# Circuit.net
KiCad netlist of a schematic drawn in EAGLE
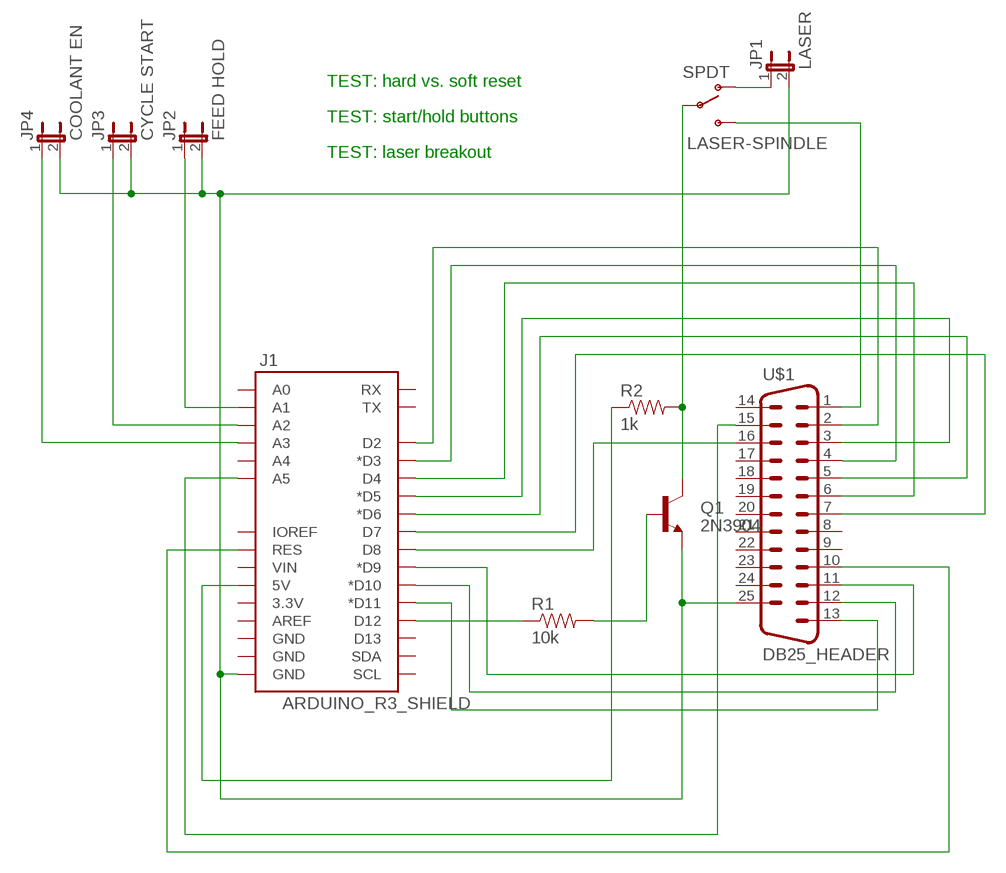
[diagram p0: schematic, sheet 1]

(export (version "E")
  (design (tool "Eeschema 10.0.6"))
  (components
    (comp (ref "J1")
      (value "ARDUINO_R3_SHIELD")
      (footprint "eagle-import:UNO_R3_SHIELD")
      (libsource (lib "eagle-import") (part "ARDUINO_R3_SHIELD"))
    )
    (comp (ref "JP1")
      (value "LASER")
      (footprint "eagle-import:1X02")
      (libsource (lib "eagle-import") (part "JUMPER-2PTH"))
    )
    (comp (ref "JP2")
      (value "FEED HOLD")
      (footprint "eagle-import:1X02")
      (libsource (lib "eagle-import") (part "JUMPER-2PTH"))
    )
    (comp (ref "JP3")
      (value "CYCLE START")
      (footprint "eagle-import:1X02")
      (libsource (lib "eagle-import") (part "JUMPER-2PTH"))
    )
    (comp (ref "JP4")
      (value "COOLANT EN")
      (footprint "eagle-import:1X02")
      (libsource (lib "eagle-import") (part "JUMPER-2PTH"))
    )
    (comp (ref "LASER-SPINDLE")
      (value "SPDT")
      (footprint "eagle-import:SWITCH-SPDT")
      (libsource (lib "eagle-import") (part "SWITCH-SPDTPTH"))
    )
    (comp (ref "Q1")
      (value "2N3904")
      (footprint "eagle-import:TO-92-AMMO")
      (libsource (lib "eagle-import") (part "TRANSISTOR_NPNBC547"))
    )
    (comp (ref "R1")
      (value "10k")
      (footprint "eagle-import:AXIAL-0.4")
      (libsource (lib "eagle-import") (part "RESISTORPTH-1/4W"))
    )
    (comp (ref "R2")
      (value "1k")
      (footprint "eagle-import:AXIAL-0.4")
      (libsource (lib "eagle-import") (part "RESISTORPTH-1/4W"))
    )
    (comp (ref "U$1")
      (value "DB25_HEADER")
      (footprint "eagle-import:DB25_HEADER")
      (libsource (lib "eagle-import") (part "DB25_HEADER"))
    )
  )
  (nets
    (net (code "1") (name "Net-(J1-*D3)") (class "Default")
      (node (ref "J1") (pin "D3") (pinfunction "*D3_D3") (pintype "bidirectional"))
      (node (ref "U$1") (pin "4") (pinfunction "4_4") (pintype "passive"))
    )
    (net (code "2") (name "Net-(J1-*D5)") (class "Default")
      (node (ref "J1") (pin "D5") (pinfunction "*D5_D5") (pintype "bidirectional"))
      (node (ref "U$1") (pin "3") (pinfunction "3_3") (pintype "passive"))
    )
    (net (code "3") (name "Net-(J1-*D6)") (class "Default")
      (node (ref "J1") (pin "D6") (pinfunction "*D6_D6") (pintype "bidirectional"))
      (node (ref "U$1") (pin "5") (pinfunction "5_5") (pintype "passive"))
    )
    (net (code "4") (name "Net-(J1-*D9)") (class "Default")
      (node (ref "J1") (pin "D9") (pinfunction "*D9_D9") (pintype "bidirectional"))
      (node (ref "U$1") (pin "11") (pinfunction "11_11") (pintype "passive"))
    )
    (net (code "5") (name "Net-(J1-*D10)") (class "Default")
      (node (ref "J1") (pin "D10") (pinfunction "*D10_D10") (pintype "bidirectional"))
      (node (ref "U$1") (pin "12") (pinfunction "12_12") (pintype "passive"))
    )
    (net (code "6") (name "Net-(J1-*D11)") (class "Default")
      (node (ref "J1") (pin "D11") (pinfunction "*D11_D11") (pintype "bidirectional"))
      (node (ref "U$1") (pin "13") (pinfunction "13_13") (pintype "passive"))
    )
    (net (code "7") (name "Net-(J1-PadA1)") (class "Default")
      (node (ref "J1") (pin "A1") (pinfunction "A1_A1") (pintype "bidirectional"))
      (node (ref "JP2") (pin "1") (pinfunction "1_1") (pintype "passive"))
    )
    (net (code "8") (name "Net-(J1-PadA2)") (class "Default")
      (node (ref "J1") (pin "A2") (pinfunction "A2_A2") (pintype "bidirectional"))
      (node (ref "JP3") (pin "1") (pinfunction "1_1") (pintype "passive"))
    )
    (net (code "9") (name "Net-(J1-PadA3)") (class "Default")
      (node (ref "J1") (pin "A3") (pinfunction "A3_A3") (pintype "bidirectional"))
      (node (ref "JP4") (pin "1") (pinfunction "1_1") (pintype "passive"))
    )
    (net (code "10") (name "Net-(J1-PadA5)") (class "Default")
      (node (ref "J1") (pin "A5") (pinfunction "A5_A5") (pintype "bidirectional"))
      (node (ref "U$1") (pin "15") (pinfunction "15_15") (pintype "passive"))
    )
    (net (code "11") (name "Net-(J1-PadD2)") (class "Default")
      (node (ref "J1") (pin "D2") (pinfunction "D2_D2") (pintype "bidirectional"))
      (node (ref "U$1") (pin "2") (pinfunction "2_2") (pintype "passive"))
    )
    (net (code "12") (name "Net-(J1-PadD4)") (class "Default")
      (node (ref "J1") (pin "D4") (pinfunction "D4_D4") (pintype "bidirectional"))
      (node (ref "U$1") (pin "6") (pinfunction "6_6") (pintype "passive"))
    )
    (net (code "13") (name "Net-(J1-PadD7)") (class "Default")
      (node (ref "J1") (pin "D7") (pinfunction "D7_D7") (pintype "bidirectional"))
      (node (ref "U$1") (pin "7") (pinfunction "7_7") (pintype "passive"))
    )
    (net (code "14") (name "Net-(J1-PadD8)") (class "Default")
      (node (ref "J1") (pin "D8") (pinfunction "D8_D8") (pintype "bidirectional"))
      (node (ref "U$1") (pin "16") (pinfunction "16_16") (pintype "passive"))
    )
    (net (code "15") (name "Net-(J1-PadRES)") (class "Default")
      (node (ref "J1") (pin "RES") (pinfunction "RES_RES") (pintype "bidirectional"))
      (node (ref "U$1") (pin "10") (pinfunction "10_10") (pintype "passive"))
    )
    (net (code "16") (name "Net-(LASER-SPINDLE-O)") (class "Default")
      (node (ref "JP1") (pin "1") (pinfunction "1_1") (pintype "passive"))
      (node (ref "LASER-SPINDLE") (pin "1") (pinfunction "O_1") (pintype "passive"))
    )
    (net (code "17") (name "Net-(LASER-SPINDLE-P)") (class "Default")
      (node (ref "LASER-SPINDLE") (pin "2") (pinfunction "P_2") (pintype "passive"))
      (node (ref "Q1") (pin "1") (pinfunction "C_1") (pintype "passive"))
      (node (ref "R2") (pin "P$2") (pinfunction "2_P$2") (pintype "passive"))
    )
    (net (code "18") (name "Net-(LASER-SPINDLE-S)") (class "Default")
      (node (ref "LASER-SPINDLE") (pin "3") (pinfunction "S_3") (pintype "passive"))
      (node (ref "U$1") (pin "1") (pinfunction "1_1") (pintype "passive"))
    )
    (net (code "19") (name "Net-(Q1-B)") (class "Default")
      (node (ref "Q1") (pin "2") (pinfunction "B_2") (pintype "passive"))
      (node (ref "R1") (pin "P$2") (pinfunction "2_P$2") (pintype "passive"))
    )
    (net (code "20") (name "Net-(Q1-E)") (class "Default")
      (node (ref "J1") (pin "GND@0") (pinfunction "GND_GND@0") (pintype "bidirectional"))
      (node (ref "JP1") (pin "2") (pinfunction "2_2") (pintype "passive"))
      (node (ref "JP2") (pin "2") (pinfunction "2_2") (pintype "passive"))
      (node (ref "JP3") (pin "2") (pinfunction "2_2") (pintype "passive"))
      (node (ref "JP4") (pin "2") (pinfunction "2_2") (pintype "passive"))
      (node (ref "Q1") (pin "3") (pinfunction "E_3") (pintype "passive"))
      (node (ref "U$1") (pin "25") (pinfunction "25_25") (pintype "passive"))
    )
    (net (code "21") (name "Net-(R1-1)") (class "Default")
      (node (ref "J1") (pin "D12") (pinfunction "D12_D12") (pintype "bidirectional"))
      (node (ref "R1") (pin "P$1") (pinfunction "1_P$1") (pintype "passive"))
    )
    (net (code "22") (name "Net-(R2-1)") (class "Default")
      (node (ref "J1") (pin "5V") (pinfunction "5V_5V") (pintype "bidirectional"))
      (node (ref "R2") (pin "P$1") (pinfunction "1_P$1") (pintype "passive"))
    )
    (net (code "23") (name "unconnected-(J1-GND-PadGND@1)") (class "Default")
      (node (ref "J1") (pin "GND@1") (pinfunction "GND_GND@1") (pintype "bidirectional"))
    )
    (net (code "24") (name "unconnected-(J1-GND-PadGND@2)") (class "Default")
      (node (ref "J1") (pin "GND@2") (pinfunction "GND_GND@2") (pintype "bidirectional"))
    )
    (net (code "25") (name "unconnected-(J1-Pad3.3V)") (class "Default")
      (node (ref "J1") (pin "3.3V") (pinfunction "3.3V_3.3V") (pintype "bidirectional"))
    )
    (net (code "26") (name "unconnected-(J1-PadA0)") (class "Default")
      (node (ref "J1") (pin "A0") (pinfunction "A0_A0") (pintype "bidirectional"))
    )
    (net (code "27") (name "unconnected-(J1-PadA4)") (class "Default")
      (node (ref "J1") (pin "A4") (pinfunction "A4_A4") (pintype "bidirectional"))
    )
    (net (code "28") (name "unconnected-(J1-PadAREF)") (class "Default")
      (node (ref "J1") (pin "AREF") (pinfunction "AREF_AREF") (pintype "bidirectional"))
    )
    (net (code "29") (name "unconnected-(J1-PadD13)") (class "Default")
      (node (ref "J1") (pin "D13") (pinfunction "D13_D13") (pintype "bidirectional"))
    )
    (net (code "30") (name "unconnected-(J1-PadIOREF)") (class "Default")
      (node (ref "J1") (pin "IOREF") (pinfunction "IOREF_IOREF") (pintype "bidirectional"))
    )
    (net (code "31") (name "unconnected-(J1-PadRX)") (class "Default")
      (node (ref "J1") (pin "RX") (pinfunction "RX_RX") (pintype "bidirectional"))
    )
    (net (code "32") (name "unconnected-(J1-PadSCL)") (class "Default")
      (node (ref "J1") (pin "SCL") (pinfunction "SCL_SCL") (pintype "bidirectional"))
    )
    (net (code "33") (name "unconnected-(J1-PadSDA)") (class "Default")
      (node (ref "J1") (pin "SDA") (pinfunction "SDA_SDA") (pintype "bidirectional"))
    )
    (net (code "34") (name "unconnected-(J1-PadTX)") (class "Default")
      (node (ref "J1") (pin "TX") (pinfunction "TX_TX") (pintype "bidirectional"))
    )
    (net (code "35") (name "unconnected-(J1-PadVIN)") (class "Default")
      (node (ref "J1") (pin "VIN") (pinfunction "VIN_VIN") (pintype "bidirectional"))
    )
    (net (code "36") (name "unconnected-(U$1-Pad8)") (class "Default")
      (node (ref "U$1") (pin "8") (pinfunction "8_8") (pintype "passive"))
    )
    (net (code "37") (name "unconnected-(U$1-Pad9)") (class "Default")
      (node (ref "U$1") (pin "9") (pinfunction "9_9") (pintype "passive"))
    )
    (net (code "38") (name "unconnected-(U$1-Pad14)") (class "Default")
      (node (ref "U$1") (pin "14") (pinfunction "14_14") (pintype "passive"))
    )
    (net (code "39") (name "unconnected-(U$1-Pad17)") (class "Default")
      (node (ref "U$1") (pin "17") (pinfunction "17_17") (pintype "passive"))
    )
    (net (code "40") (name "unconnected-(U$1-Pad18)") (class "Default")
      (node (ref "U$1") (pin "18") (pinfunction "18_18") (pintype "passive"))
    )
    (net (code "41") (name "unconnected-(U$1-Pad19)") (class "Default")
      (node (ref "U$1") (pin "19") (pinfunction "19_19") (pintype "passive"))
    )
    (net (code "42") (name "unconnected-(U$1-Pad20)") (class "Default")
      (node (ref "U$1") (pin "20") (pinfunction "20_20") (pintype "passive"))
    )
    (net (code "43") (name "unconnected-(U$1-Pad21)") (class "Default")
      (node (ref "U$1") (pin "21") (pinfunction "21_21") (pintype "passive"))
    )
    (net (code "44") (name "unconnected-(U$1-Pad22)") (class "Default")
      (node (ref "U$1") (pin "22") (pinfunction "22_22") (pintype "passive"))
    )
    (net (code "45") (name "unconnected-(U$1-Pad23)") (class "Default")
      (node (ref "U$1") (pin "23") (pinfunction "23_23") (pintype "passive"))
    )
    (net (code "46") (name "unconnected-(U$1-Pad24)") (class "Default")
      (node (ref "U$1") (pin "24") (pinfunction "24_24") (pintype "passive"))
    )
  )
)
